# SoC_Jtag.net
KiCad netlist of a schematic drawn in Altium Designer
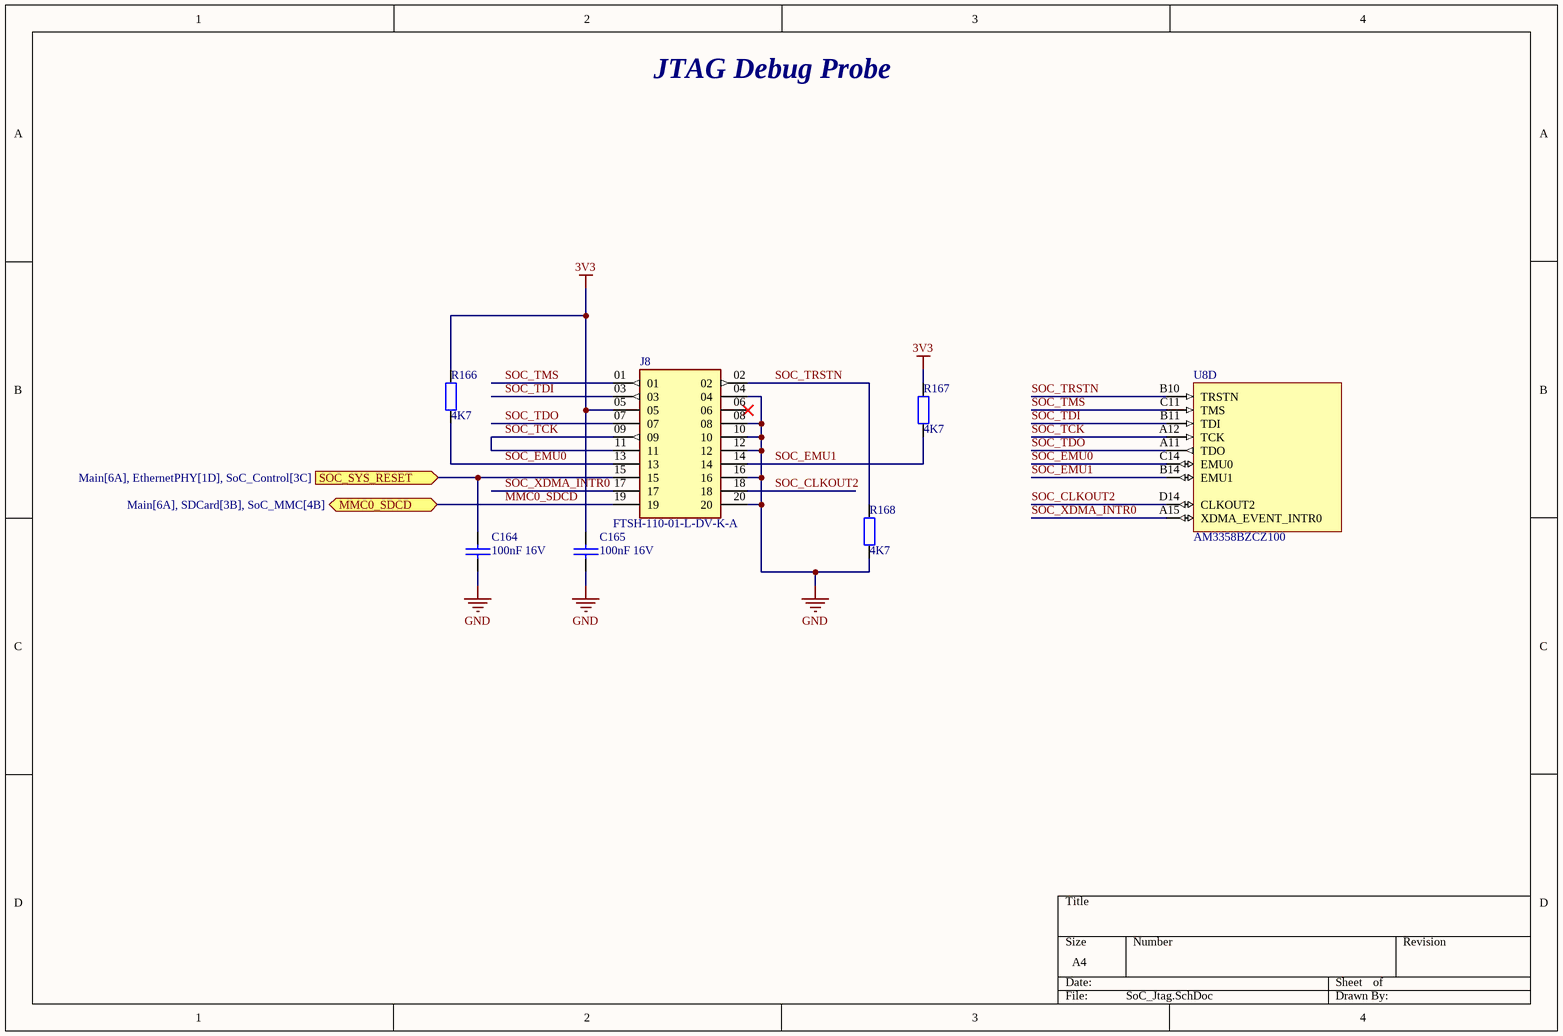
[diagram p0: SoC_Jtag.SchDoc]

(export (version "E")
  (design (tool "Eeschema 10.0.6"))
  (components
    (comp (ref "C164")
      (value "100nF 16V")
      (footprint "C_0402")
      (description "Capacitor 0402 SMD")
      (libsource (lib "tor1kkLib") (part "C_0402"))
    )
    (comp (ref "C165")
      (value "100nF 16V")
      (footprint "C_0402")
      (description "Capacitor 0402 SMD")
      (libsource (lib "tor1kkLib") (part "C_0402"))
    )
    (comp (ref "J8")
      (value "FTSH-110-01-L-DV-K-A")
      (footprint "FTSH-110-01-L-DV-K-A")
      (description "Connector Header Surface Mount 20 position 0.050\" (1.27mm)")
      (libsource (lib "tor1kkLib") (part "FTSH-110-01-L-DV-K-A"))
    )
    (comp (ref "R166")
      (value "4K7")
      (footprint "R_0402")
      (description "Resistor 0402 SMD")
      (libsource (lib "tor1kkLib") (part "R_0402"))
    )
    (comp (ref "R167")
      (value "4K7")
      (footprint "R_0402")
      (description "Resistor 0402 SMD")
      (libsource (lib "tor1kkLib") (part "R_0402"))
    )
    (comp (ref "R168")
      (value "4K7")
      (footprint "R_0402")
      (description "Resistor 0402 SMD")
      (libsource (lib "tor1kkLib") (part "R_0402"))
    )
    (comp (ref "U8")
      (value "AM3358BZCZ100")
      (footprint "BGA324C80P18X18_1500X1500X140")
      (description "ARM-ASeries 1GHz NFBGA-324 Microcontrollers (MCU/MPU/SOC) ROHS")
      (fields (field (name "MANUFACTURER") "Texas Instruments"))
      (libsource (lib "tor1kkLib") (part "AM3358BZCZ100"))
    )
  )
  (nets
    (net (code "1") (name "/MMC0_SDCD") (class "Default")
      (node (ref "J8") (pin "19") (pinfunction "19_19") (pintype "passive"))
    )
    (net (code "2") (name "/SOC_CLKOUT2") (class "Default")
      (node (ref "J8") (pin "18") (pinfunction "18_18") (pintype "passive"))
      (node (ref "U8") (pin "D14") (pinfunction "CLKOUT2_D14") (pintype "bidirectional"))
    )
    (net (code "3") (name "/SOC_EMU0") (class "Default")
      (node (ref "J8") (pin "13") (pinfunction "13_13") (pintype "passive"))
      (node (ref "R166") (pin "1") (pintype "passive"))
      (node (ref "U8") (pin "C14") (pinfunction "EMU0_C14") (pintype "bidirectional"))
    )
    (net (code "4") (name "/SOC_EMU1") (class "Default")
      (node (ref "J8") (pin "14") (pinfunction "14_14") (pintype "passive"))
      (node (ref "R167") (pin "1") (pintype "passive"))
      (node (ref "U8") (pin "B14") (pinfunction "EMU1_B14") (pintype "bidirectional"))
    )
    (net (code "5") (name "/SOC_SYS_RESET") (class "Default")
      (node (ref "C164") (pin "1") (pintype "passive"))
      (node (ref "J8") (pin "15") (pinfunction "15_15") (pintype "passive"))
    )
    (net (code "6") (name "/SOC_TCK") (class "Default")
      (node (ref "J8") (pin "09") (pinfunction "09_09") (pintype "output"))
      (node (ref "J8") (pin "11") (pinfunction "11_11") (pintype "passive"))
      (node (ref "U8") (pin "A12") (pinfunction "TCK_A12") (pintype "input"))
    )
    (net (code "7") (name "/SOC_TDI") (class "Default")
      (node (ref "J8") (pin "03") (pinfunction "03_03") (pintype "output"))
      (node (ref "U8") (pin "B11") (pinfunction "TDI_B11") (pintype "input"))
    )
    (net (code "8") (name "/SOC_TDO") (class "Default")
      (node (ref "J8") (pin "07") (pinfunction "07_07") (pintype "passive"))
      (node (ref "U8") (pin "A11") (pinfunction "TDO_A11") (pintype "output"))
    )
    (net (code "9") (name "/SOC_TMS") (class "Default")
      (node (ref "J8") (pin "01") (pinfunction "01_01") (pintype "output"))
      (node (ref "U8") (pin "C11") (pinfunction "TMS_C11") (pintype "input"))
    )
    (net (code "10") (name "/SOC_TRSTN") (class "Default")
      (node (ref "J8") (pin "02") (pinfunction "02_02") (pintype "output"))
      (node (ref "R168") (pin "2") (pintype "passive"))
      (node (ref "U8") (pin "B10") (pinfunction "TRSTN_B10") (pintype "input"))
    )
    (net (code "11") (name "/SOC_XDMA_INTR0") (class "Default")
      (node (ref "J8") (pin "17") (pinfunction "17_17") (pintype "passive"))
      (node (ref "U8") (pin "A15") (pinfunction "XDMA_EVENT_INTR0_A15") (pintype "bidirectional"))
    )
    (net (code "12") (name "3V3") (class "Default")
      (node (ref "C165") (pin "1") (pintype "passive"))
      (node (ref "J8") (pin "05") (pinfunction "05_05") (pintype "passive"))
      (node (ref "R166") (pin "2") (pintype "passive"))
      (node (ref "R167") (pin "2") (pintype "passive"))
    )
    (net (code "13") (name "GND") (class "Default")
      (node (ref "C164") (pin "2") (pintype "passive"))
      (node (ref "C165") (pin "2") (pintype "passive"))
      (node (ref "J8") (pin "04") (pinfunction "04_04") (pintype "passive"))
      (node (ref "J8") (pin "08") (pinfunction "08_08") (pintype "passive"))
      (node (ref "J8") (pin "10") (pinfunction "10_10") (pintype "passive"))
      (node (ref "J8") (pin "12") (pinfunction "12_12") (pintype "passive"))
      (node (ref "J8") (pin "16") (pinfunction "16_16") (pintype "passive"))
      (node (ref "J8") (pin "20") (pinfunction "20_20") (pintype "passive"))
      (node (ref "R168") (pin "1") (pintype "passive"))
    )
    (net (code "14") (name "unconnected-(J8-Pad06)") (class "Default")
      (node (ref "J8") (pin "06") (pinfunction "06_06") (pintype "passive+no_connect"))
    )
  )
)
